# Power_CU_Schematic.net
KiCad netlist of a schematic drawn in Altium Designer
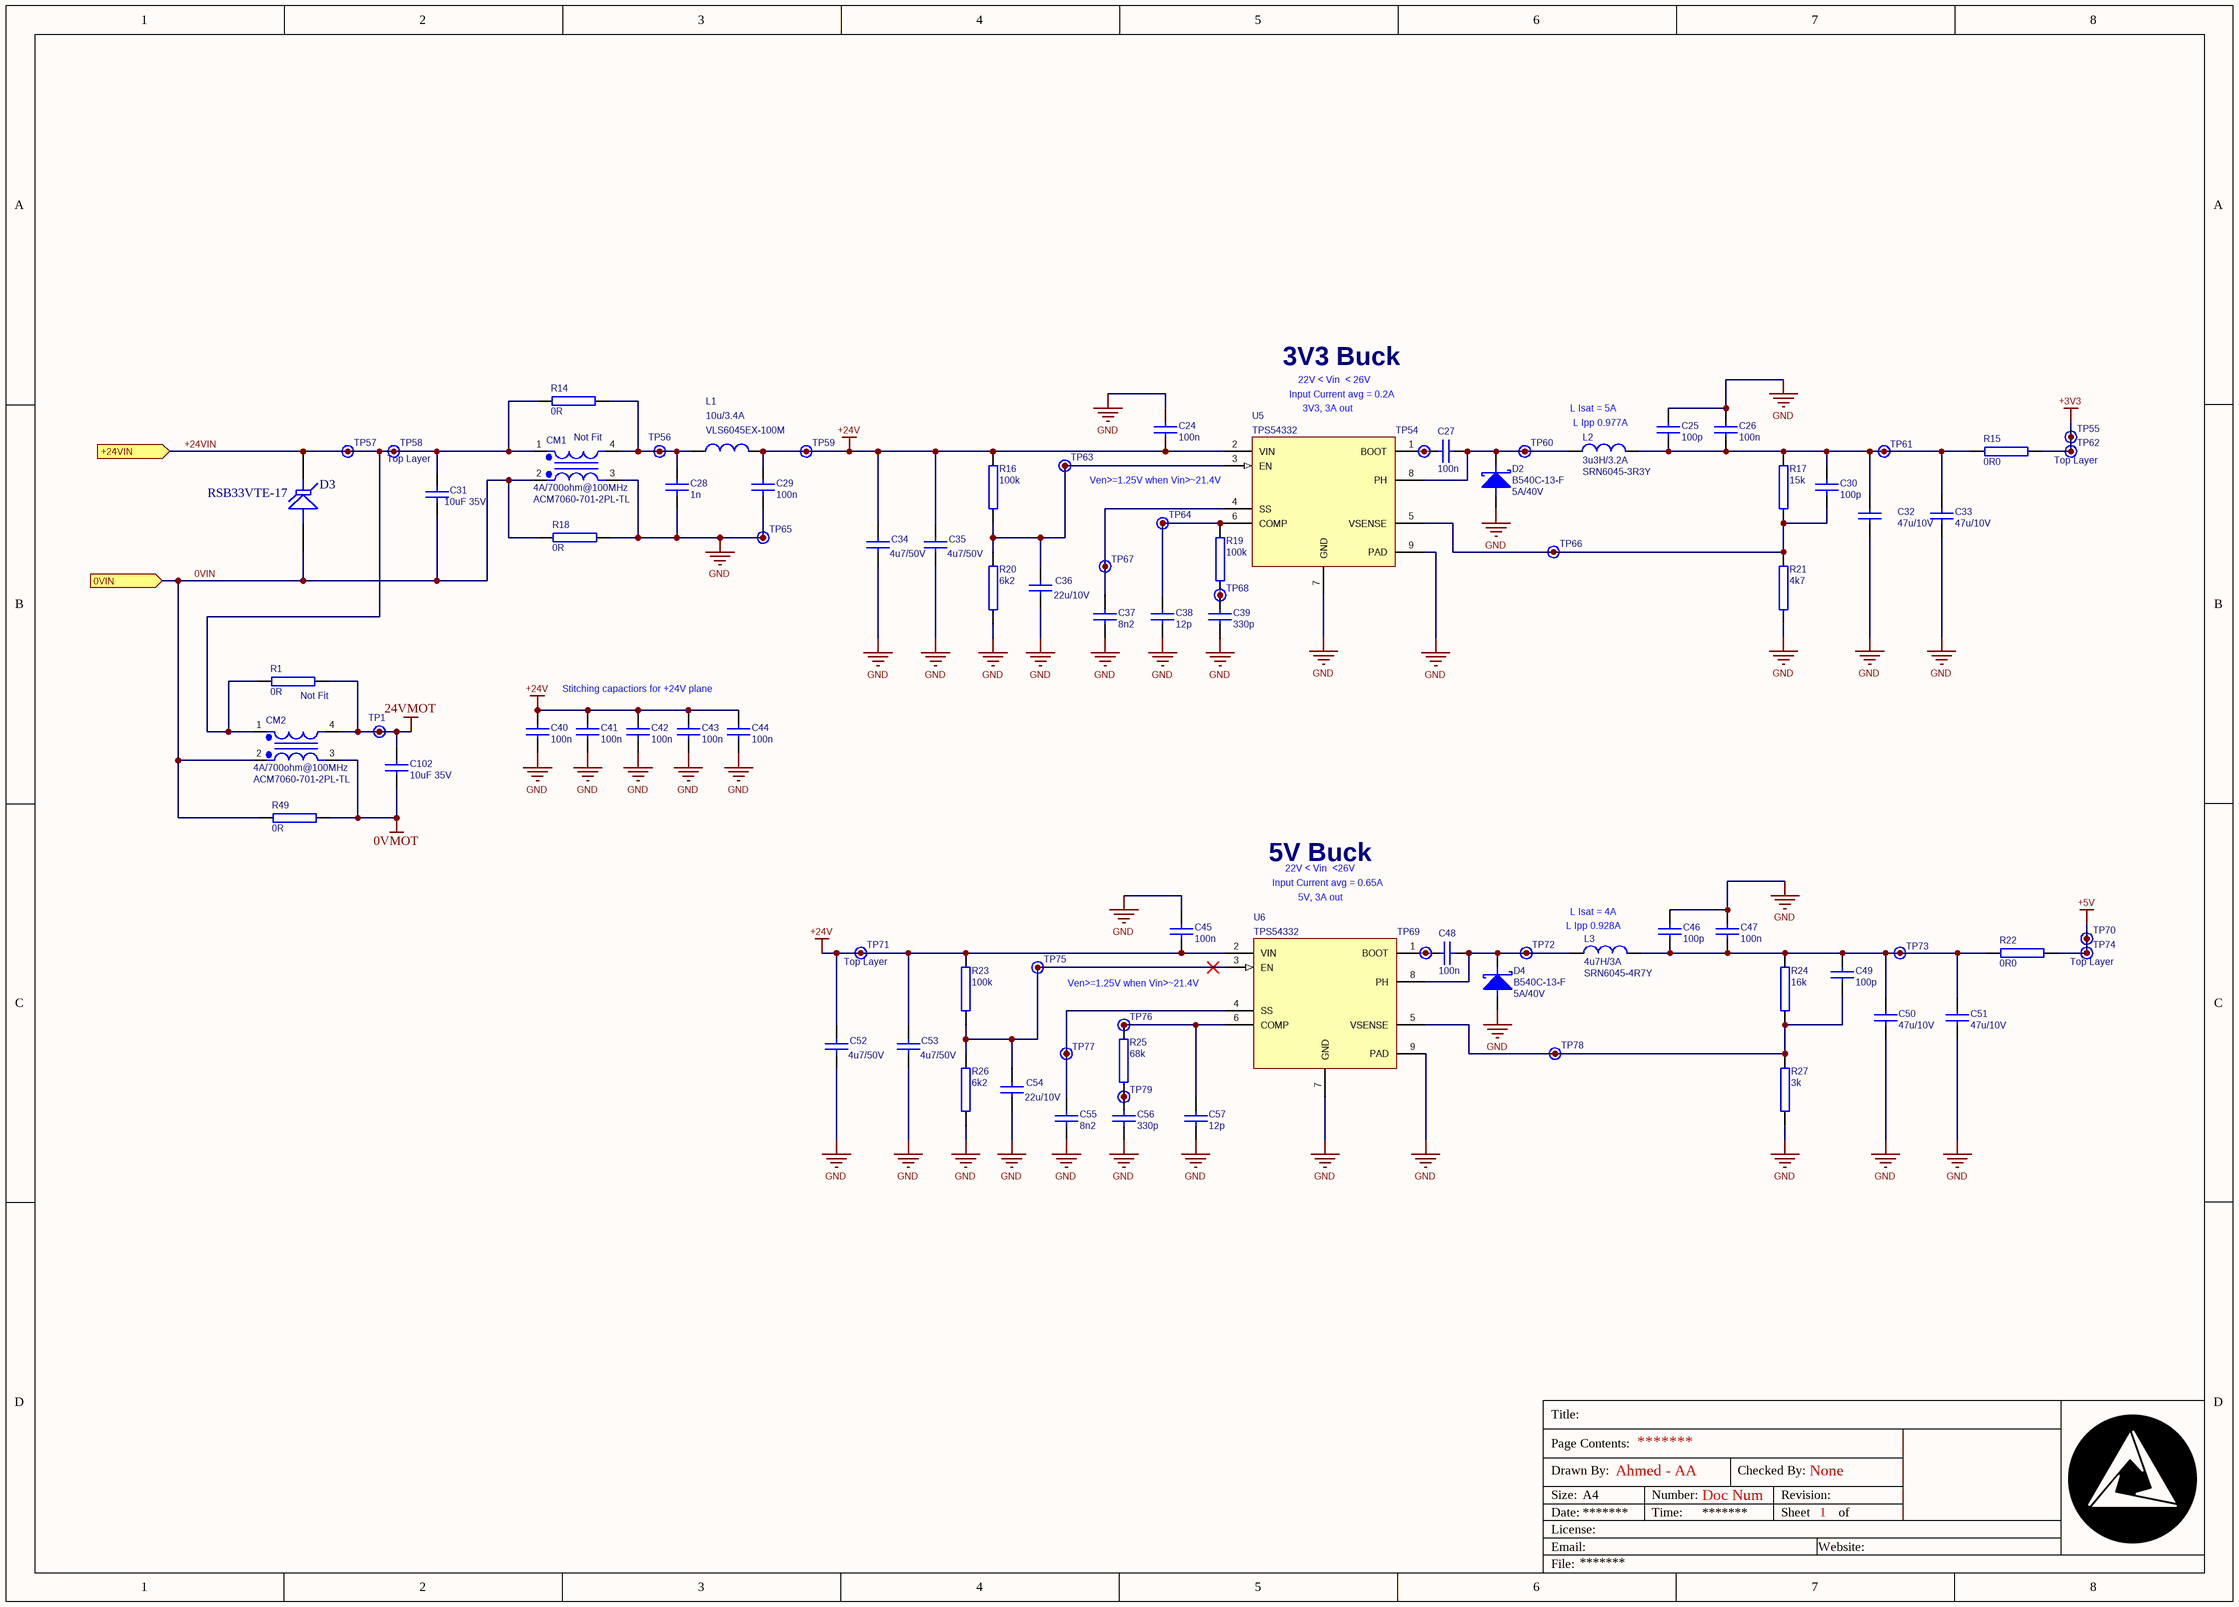
[diagram p0: Power_CU Schematic.SchDoc]

(export (version "E")
  (design (tool "Eeschema 10.0.6"))
  (components
    (comp (ref "C24")
      (value "100n")
      (footprint "CAPC1608X09N(0603)")
      (description "Capacitor, Ceramic, 50V, ±10%, X7R, -55°C to 125°C")
      (fields (field (name "02 PART NUMBER") "GRM188R71H104KA93D") (field (name "12 AUTHOR") "D.Grace"))
      (libsource (lib "Ingenuity Master Capacitor Schematic Library") (part "GRM188R71H104KA93D"))
    )
    (comp (ref "C25")
      (value "100p")
      (footprint "CAPC1608X09N(0603)")
      (description "Capacitor, Ceramic, 50V, ±5%, C0G NP0, -55°C to 125°C")
      (fields (field (name "02 PART NUMBER") "GRM1885C1H101JA01D") (field (name "12 AUTHOR") "D.Grace"))
      (libsource (lib "Ingenuity Master Capacitor Schematic Library") (part "GRM1885C1H101JA01D"))
    )
    (comp (ref "C26")
      (value "100n")
      (footprint "CAPC1608X09N(0603)")
      (description "Capacitor, Ceramic, 50V, ±10%, X7R, -55°C to 125°C")
      (fields (field (name "02 PART NUMBER") "GRM188R71H104KA93D") (field (name "12 AUTHOR") "D.Grace"))
      (libsource (lib "Ingenuity Master Capacitor Schematic Library") (part "GRM188R71H104KA93D"))
    )
    (comp (ref "C27")
      (value "100n")
      (footprint "CAPC1608X09N(0603)")
      (description "Capacitor, Ceramic, 50V, ±10%, X7R, -55°C to 125°C")
      (fields (field (name "02 PART NUMBER") "GRM188R71H104KA93D") (field (name "12 AUTHOR") "D.Grace"))
      (libsource (lib "Ingenuity Master Capacitor Schematic Library") (part "GRM188R71H104KA93D"))
    )
    (comp (ref "C28")
      (value "1n")
      (footprint "CAPC1608X09N(0603)")
      (description "Capacitor, Ceramic, 50V, ±5%, C0G NP0, -55°C to 125°C")
      (fields (field (name "02 PART NUMBER") "GRM1885C1H102JA01D") (field (name "12 AUTHOR") "D.Grace"))
      (libsource (lib "Ingenuity Master Capacitor Schematic Library") (part "GRM1885C1H102JA01D"))
    )
    (comp (ref "C29")
      (value "100n")
      (footprint "CAPC1608X09N(0603)")
      (description "Capacitor, Ceramic, 50V, ±10%, X7R, -55°C to 125°C")
      (fields (field (name "02 PART NUMBER") "GRM188R71H104KA93D") (field (name "12 AUTHOR") "D.Grace"))
      (libsource (lib "Ingenuity Master Capacitor Schematic Library") (part "GRM188R71H104KA93D"))
    )
    (comp (ref "C30")
      (value "100p")
      (footprint "CAPC1608X09N(0603)")
      (description "Capacitor, Ceramic, 50V, ±5%, C0G NP0, -55°C to 125°C")
      (fields (field (name "02 PART NUMBER") "GRM1885C1H101JA01D") (field (name "12 AUTHOR") "D.Grace"))
      (libsource (lib "Ingenuity Master Capacitor Schematic Library") (part "GRM1885C1H101JA01D"))
    )
    (comp (ref "C31")
      (value "10uF 35V")
      (footprint "CAPC1608X09N(0603)")
      (description "Capacitor, Ceramic, 50V, ±20%,")
      (fields (field (name "02 PART NUMBER") "GRM1885C1H102JA01D") (field (name "12 AUTHOR") "D.Grace"))
      (libsource (lib "Ingenuity Master Capacitor Schematic Library") (part "GRM1885C1H102JA01D"))
    )
    (comp (ref "C32")
      (value "47u/10V")
      (footprint "CAPC2012X13N(0805)")
      (description "Capacitor, Ceramic, 10V, ±20%, X5R, -55°C to 85°C")
      (fields (field (name "02 PART NUMBER") "C2012X5R1A476M125AC") (field (name "12 AUTHOR") "K.Sukumar"))
      (libsource (lib "Ingenuity Master Capacitor Schematic Library") (part "C2012X5R1A476M125AC"))
    )
    (comp (ref "C33")
      (value "47u/10V")
      (footprint "CAPC2012X13N(0805)")
      (description "Capacitor, Ceramic, 10V, ±20%, X5R, -55°C to 85°C")
      (fields (field (name "02 PART NUMBER") "C2012X5R1A476M125AC") (field (name "12 AUTHOR") "K.Sukumar"))
      (libsource (lib "Ingenuity Master Capacitor Schematic Library") (part "C2012X5R1A476M125AC"))
    )
    (comp (ref "C34")
      (value "Cin")
      (footprint "CAPC3216X16N(1206)")
      (description "Capacitor, Ceramic, 50V, ±10%, X7R, -55°C to 125°C")
      (fields
        (field (name "02 PART NUMBER") "GRM31CR71H475KA12L")
        (field (name "04 VALUE") "4u7/50V")
        (field (name "12 AUTHOR") "D.Grace")
      )
      (libsource (lib "Ingenuity Master Capacitor Schematic Library") (part "GRM31CR71H475KA12L"))
    )
    (comp (ref "C35")
      (value "Cin")
      (footprint "CAPC3216X16N(1206)")
      (description "Capacitor, Ceramic, 50V, ±10%, X7R, -55°C to 125°C")
      (fields
        (field (name "02 PART NUMBER") "GRM31CR71H475KA12L")
        (field (name "04 VALUE") "4u7/50V")
        (field (name "12 AUTHOR") "D.Grace")
      )
      (libsource (lib "Ingenuity Master Capacitor Schematic Library") (part "GRM31CR71H475KA12L"))
    )
    (comp (ref "C36")
      (value "22u/10V")
      (footprint "CAPC1608X09N(0603)")
      (description "Capacitor, Ceramic, 10V, ±20%, X5R, -55°C to 85°C")
      (fields (field (name "02 PART NUMBER") "C1608X5R1A226M080AC") (field (name "12 AUTHOR") "K.Sukumar"))
      (libsource (lib "Ingenuity Master Capacitor Schematic Library") (part "C1608X5R1A226M080AC"))
    )
    (comp (ref "C37")
      (value "8n2")
      (footprint "CAPC1608X09N(0603)")
      (description "Capacitor, Ceramic, 50V, ±10%, X7R, -55°C to 125°C")
      (fields (field (name "02 PART NUMBER") "GRM188R71H822KA01D") (field (name "12 AUTHOR") "D.Grace"))
      (libsource (lib "Ingenuity Master Capacitor Schematic Library") (part "GRM188R71H822KA01D"))
    )
    (comp (ref "C38")
      (value "12p")
      (footprint "CAPC1608X09N(0603)")
      (description "Capacitor, Ceramic, 50V, ±5%, C0G NP0, -55°C to 125°C")
      (fields (field (name "02 PART NUMBER") "GRM1885C1H120JA01D") (field (name "12 AUTHOR") "D.Grace"))
      (libsource (lib "Ingenuity Master Capacitor Schematic Library") (part "GRM1885C1H120JA01D"))
    )
    (comp (ref "C39")
      (value "330p")
      (footprint "CAPC1608X09N(0603)")
      (description "Capacitor, Ceramic, 50V, ±10%, X7R, -55°C to 125°C")
      (fields (field (name "02 PART NUMBER") "GRM188R71H331KA01D") (field (name "12 AUTHOR") "M.Fineschi"))
      (libsource (lib "D0001310 Trophon EPR GUI Carrier Board Schematic Library (1_0)") (part "GRM188R71H331KA01D"))
    )
    (comp (ref "C40")
      (value "100n")
      (footprint "CAPC1608X09N(0603)")
      (description "Capacitor, Ceramic, 50V, ±10%, X7R, -55°C to 125°C")
      (fields (field (name "02 PART NUMBER") "GRM188R71H104KA93D") (field (name "12 AUTHOR") "D.Grace"))
      (libsource (lib "Ingenuity Master Capacitor Schematic Library") (part "GRM188R71H104KA93D"))
    )
    (comp (ref "C41")
      (value "100n")
      (footprint "CAPC1608X09N(0603)")
      (description "Capacitor, Ceramic, 50V, ±10%, X7R, -55°C to 125°C")
      (fields (field (name "02 PART NUMBER") "GRM188R71H104KA93D") (field (name "12 AUTHOR") "D.Grace"))
      (libsource (lib "Ingenuity Master Capacitor Schematic Library") (part "GRM188R71H104KA93D"))
    )
    (comp (ref "C42")
      (value "100n")
      (footprint "CAPC1608X09N(0603)")
      (description "Capacitor, Ceramic, 50V, ±10%, X7R, -55°C to 125°C")
      (fields (field (name "02 PART NUMBER") "GRM188R71H104KA93D") (field (name "12 AUTHOR") "D.Grace"))
      (libsource (lib "Ingenuity Master Capacitor Schematic Library") (part "GRM188R71H104KA93D"))
    )
    (comp (ref "C43")
      (value "100n")
      (footprint "CAPC1608X09N(0603)")
      (description "Capacitor, Ceramic, 50V, ±10%, X7R, -55°C to 125°C")
      (fields (field (name "02 PART NUMBER") "GRM188R71H104KA93D") (field (name "12 AUTHOR") "D.Grace"))
      (libsource (lib "Ingenuity Master Capacitor Schematic Library") (part "GRM188R71H104KA93D"))
    )
    (comp (ref "C44")
      (value "100n")
      (footprint "CAPC1608X09N(0603)")
      (description "Capacitor, Ceramic, 50V, ±10%, X7R, -55°C to 125°C")
      (fields (field (name "02 PART NUMBER") "GRM188R71H104KA93D") (field (name "12 AUTHOR") "D.Grace"))
      (libsource (lib "Ingenuity Master Capacitor Schematic Library") (part "GRM188R71H104KA93D"))
    )
    (comp (ref "C45")
      (value "100n")
      (footprint "CAPC1608X09N(0603)")
      (description "Capacitor, Ceramic, 50V, ±10%, X7R, -55°C to 125°C")
      (fields (field (name "02 PART NUMBER") "GRM188R71H104KA93D") (field (name "12 AUTHOR") "D.Grace"))
      (libsource (lib "Ingenuity Master Capacitor Schematic Library") (part "GRM188R71H104KA93D"))
    )
    (comp (ref "C46")
      (value "100p")
      (footprint "CAPC1608X09N(0603)")
      (description "Capacitor, Ceramic, 50V, ±5%, C0G NP0, -55°C to 125°C")
      (fields (field (name "02 PART NUMBER") "GRM1885C1H101JA01D") (field (name "12 AUTHOR") "D.Grace"))
      (libsource (lib "Ingenuity Master Capacitor Schematic Library") (part "GRM1885C1H101JA01D"))
    )
    (comp (ref "C47")
      (value "100n")
      (footprint "CAPC1608X09N(0603)")
      (description "Capacitor, Ceramic, 50V, ±10%, X7R, -55°C to 125°C")
      (fields (field (name "02 PART NUMBER") "GRM188R71H104KA93D") (field (name "12 AUTHOR") "D.Grace"))
      (libsource (lib "Ingenuity Master Capacitor Schematic Library") (part "GRM188R71H104KA93D"))
    )
    (comp (ref "C48")
      (value "100n")
      (footprint "CAPC1608X09N(0603)")
      (description "Capacitor, Ceramic, 50V, ±10%, X7R, -55°C to 125°C")
      (fields (field (name "02 PART NUMBER") "GRM188R71H104KA93D") (field (name "12 AUTHOR") "D.Grace"))
      (libsource (lib "Ingenuity Master Capacitor Schematic Library") (part "GRM188R71H104KA93D"))
    )
    (comp (ref "C49")
      (value "100p")
      (footprint "CAPC1608X09N(0603)")
      (description "Capacitor, Ceramic, 50V, ±5%, C0G NP0, -55°C to 125°C")
      (fields (field (name "02 PART NUMBER") "GRM1885C1H101JA01D") (field (name "12 AUTHOR") "D.Grace"))
      (libsource (lib "Ingenuity Master Capacitor Schematic Library") (part "GRM1885C1H101JA01D"))
    )
    (comp (ref "C50")
      (value "47u/10V")
      (footprint "CAPC2012X13N(0805)")
      (description "Capacitor, Ceramic, 10V, ±20%, X5R, -55°C to 85°C")
      (fields (field (name "02 PART NUMBER") "C2012X5R1A476M125AC") (field (name "12 AUTHOR") "K.Sukumar"))
      (libsource (lib "Ingenuity Master Capacitor Schematic Library") (part "C2012X5R1A476M125AC"))
    )
    (comp (ref "C51")
      (value "47u/10V")
      (footprint "CAPC2012X13N(0805)")
      (description "Capacitor, Ceramic, 10V, ±20%, X5R, -55°C to 85°C")
      (fields (field (name "02 PART NUMBER") "C2012X5R1A476M125AC") (field (name "12 AUTHOR") "K.Sukumar"))
      (libsource (lib "Ingenuity Master Capacitor Schematic Library") (part "C2012X5R1A476M125AC"))
    )
    (comp (ref "C52")
      (value "Cin")
      (footprint "CAPC3216X16N(1206)")
      (description "Capacitor, Ceramic, 50V, ±10%, X7R, -55°C to 125°C")
      (fields
        (field (name "02 PART NUMBER") "GRM31CR71H475KA12L")
        (field (name "04 VALUE") "4u7/50V")
        (field (name "12 AUTHOR") "D.Grace")
      )
      (libsource (lib "Ingenuity Master Capacitor Schematic Library") (part "GRM31CR71H475KA12L"))
    )
    (comp (ref "C53")
      (value "Cin")
      (footprint "CAPC3216X16N(1206)")
      (description "Capacitor, Ceramic, 50V, ±10%, X7R, -55°C to 125°C")
      (fields
        (field (name "02 PART NUMBER") "GRM31CR71H475KA12L")
        (field (name "04 VALUE") "4u7/50V")
        (field (name "12 AUTHOR") "D.Grace")
      )
      (libsource (lib "Ingenuity Master Capacitor Schematic Library") (part "GRM31CR71H475KA12L"))
    )
    (comp (ref "C54")
      (value "22u/10V")
      (footprint "CAPC1608X09N(0603)")
      (description "Capacitor, Ceramic, 10V, ±20%, X5R, -55°C to 85°C")
      (fields (field (name "02 PART NUMBER") "C1608X5R1A226M080AC") (field (name "12 AUTHOR") "K.Sukumar"))
      (libsource (lib "Ingenuity Master Capacitor Schematic Library") (part "C1608X5R1A226M080AC"))
    )
    (comp (ref "C55")
      (value "8n2")
      (footprint "CAPC1608X09N(0603)")
      (description "Capacitor, Ceramic, 50V, ±10%, X7R, -55°C to 125°C")
      (fields (field (name "02 PART NUMBER") "GRM188R71H822KA01D") (field (name "12 AUTHOR") "D.Grace"))
      (libsource (lib "Ingenuity Master Capacitor Schematic Library") (part "GRM188R71H822KA01D"))
    )
    (comp (ref "C56")
      (value "330p")
      (footprint "CAPC1608X09N(0603)")
      (description "Capacitor, Ceramic, 50V, ±10%, X7R, -55°C to 125°C")
      (fields (field (name "02 PART NUMBER") "GRM188R71H331KA01D") (field (name "12 AUTHOR") "M.Fineschi"))
      (libsource (lib "D0001310 Trophon EPR GUI Carrier Board Schematic Library (1_0)") (part "GRM188R71H331KA01D"))
    )
    (comp (ref "C57")
      (value "12p")
      (footprint "CAPC1608X09N(0603)")
      (description "Capacitor, Ceramic, 50V, ±5%, C0G NP0, -55°C to 125°C")
      (fields (field (name "02 PART NUMBER") "GRM1885C1H120JA01D") (field (name "12 AUTHOR") "D.Grace"))
      (libsource (lib "Ingenuity Master Capacitor Schematic Library") (part "GRM1885C1H120JA01D"))
    )
    (comp (ref "C102")
      (value "10uF 35V")
      (footprint "CAPC1608X09N(0603)")
      (description "Capacitor, Ceramic, 50V, ±5%, C0G NP0, -55°C to 125°C")
      (libsource (lib "Ingenuity Master Capacitor Schematic Library") (part "GRM1885C1H102JA01D"))
    )
    (comp (ref "CM1")
      (value "4A/700ohm@100MHz")
      (footprint "ACM7060-701-2PL-TL")
      (description "Common Mode Choke, 4A, 500ohm min 700ohm typ @100MHz, 15mOhm Max,")
      (fields
        (field (name "07 ASSEMBLY OPTIONS") "Not Fit")
        (field (name "02 PART NUMBER") "ACM7060-701-2PL-TL")
        (field (name "12 AUTHOR") "D.Grace")
      )
      (libsource (lib "Mesh Nebuliser Schematic Library") (part "ACM7060-701-2PL-TL"))
    )
    (comp (ref "CM2")
      (value "4A/700ohm@100MHz")
      (footprint "ACM7060-701-2PL-TL")
      (description "Common Mode Choke, 4A, 500ohm min 700ohm typ @100MHz, 15mOhm Max,")
      (fields
        (field (name "07 ASSEMBLY OPTIONS") "Not Fit")
        (field (name "02 PART NUMBER") "ACM7060-701-2PL-TL")
        (field (name "12 AUTHOR") "D.Grace")
      )
      (libsource (lib "Mesh Nebuliser Schematic Library") (part "ACM7060-701-2PL-TL"))
    )
    (comp (ref "D2")
      (value "B540C-13-F")
      (footprint "B540C")
      (description "Diode, Schottky, Fast Recovery, 550mV @ 5A, 40V, 5A,  500ns, -55°C - +125°C")
      (fields (field (name "04 VALUE") "5A/40V") (field (name "12 AUTHOR") "J.McLachlan"))
      (libsource (lib "D0001310 Trophon EPR GUI Carrier Board Schematic Library (1_0)") (part "B540C-13-F"))
    )
    (comp (ref "D3")
      (value "RSB33VTE-17")
      (footprint "Miscellaneous Devices:425")
      (description "Transient Voltage Suppression (TVS) Diode")
      (fields (field (name "PUBLISHER") "Altium Limited"))
      (libsource (lib "Miscellaneous Devices") (part "Tranzorb"))
    )
    (comp (ref "D4")
      (value "B540C-13-F")
      (footprint "B540C")
      (description "Diode, Schottky, Fast Recovery, 550mV @ 5A, 40V, 5A,  500ns, -55°C - +125°C")
      (fields (field (name "04 VALUE") "5A/40V") (field (name "12 AUTHOR") "J.McLachlan"))
      (libsource (lib "D0001310 Trophon EPR GUI Carrier Board Schematic Library (1_0)") (part "B540C-13-F"))
    )
    (comp (ref "L1")
      (value "10u/3.4A")
      (footprint "VLP6045LT-100M")
      (description "Inductor, 10µH , 3.4A rated, 3.9A Saturation,61mOhm")
      (fields (field (name "02 PART NUMBER") "VLS6045EX-100M") (field (name "12 AUTHOR") "M.Fineschi"))
      (libsource (lib "D0001310 Trophon EPR GUI Carrier Board Schematic Library (1_0)") (part "VLP6045LT-100M"))
    )
    (comp (ref "L2")
      (value "3u3H/3.2A")
      (footprint "SRN6045-1R0Y")
      (description "Inductor, 3u3H , I = 3.2A, 30.2mOhm, SRF 27MHz, ±30%, 5A Saturation")
      (fields (field (name "02 PART NUMBER") "SRN6045-3R3Y") (field (name "12 AUTHOR") "J.McLachlan"))
      (libsource (lib "D0001310 Trophon EPR GUI Carrier Board Schematic Library (1_0)") (part "SRN6045-3R3Y"))
    )
    (comp (ref "L3")
      (value "4u7H/3A")
      (footprint "SRN6045-1R0Y")
      (description "Inductor, 4u7H , I = 3A, 37.6mOhm, SRF 22MHz, ±30%, 4A Saturation")
      (fields (field (name "02 PART NUMBER") "SRN6045-4R7Y") (field (name "12 AUTHOR") "J.McLachlan"))
      (libsource (lib "D0001310 Trophon EPR GUI Carrier Board Schematic Library (1_0)") (part "SRN6045-4R7Y"))
    )
    (comp (ref "R1")
      (value "0R")
      (footprint "RESC3116X07N(1206)")
      (description "Resistor, Thick Film, 0.25W, ±1%, ±100ppm/°C")
      (fields (field (name "02 PART NUMBER") "RC1206JR-070RL") (field (name "12 AUTHOR") "M.Fineschi"))
      (libsource (lib "D0001310 Trophon EPR GUI Carrier Board Schematic Library (1_0)") (part "RC1206JR-070RL"))
    )
    (comp (ref "R14")
      (value "0R")
      (footprint "RESC3116X07N(1206)")
      (description "Resistor, Thick Film, 0.25W, ±1%, ±100ppm/°C")
      (fields (field (name "02 PART NUMBER") "RC1206JR-070RL") (field (name "12 AUTHOR") "M.Fineschi"))
      (libsource (lib "D0001310 Trophon EPR GUI Carrier Board Schematic Library (1_0)") (part "RC1206JR-070RL"))
    )
    (comp (ref "R15")
      (value "0R0")
      (footprint "RESC1608X06N(0603)")
      (description "Resistor, Thick Film, 0.1W, ±1%, ±100ppm/°C")
      (fields
        (field (name "02 PART NUMBER") "RC1608J000CS")
        (field (name "13 REVIEWED BY") "P.Moutzouris")
        (field (name "12 AUTHOR") "K.Sukumar")
      )
      (libsource (lib "Ingenuity Master Resistor 0603 Schematic Library") (part "RC1608J000CS"))
    )
    (comp (ref "R16")
      (value "100k")
      (footprint "RESC1608X06N(0603)")
      (description "Resistor, Thick Film, 0.1W, ±1%, ±100ppm/°C")
      (fields
        (field (name "02 PART NUMBER") "RC0603FR-07100KL")
        (field (name "13 REVIEWED BY") "P.Moutzouris")
        (field (name "12 AUTHOR") "D.Grace")
      )
      (libsource (lib "Ingenuity Master Resistor 0603 Schematic Library") (part "RC0603FR-07100KL"))
    )
    (comp (ref "R17")
      (value "15k")
      (footprint "RESC1608X06N(0603)")
      (description "Resistor, Thick Film, 0.1W, ±1%, ±100ppm/°C")
      (fields
        (field (name "02 PART NUMBER") "RC0603FR-0715KL")
        (field (name "13 REVIEWED BY") "P.Moutzouris")
        (field (name "12 AUTHOR") "D.Grace")
      )
      (libsource (lib "Ingenuity Master Resistor 0603 Schematic Library") (part "RC0603FR-0715KL"))
    )
    (comp (ref "R18")
      (value "0R")
      (footprint "RESC3116X07N(1206)")
      (description "Resistor, Thick Film, 0.25W, ±1%, ±100ppm/°C")
      (fields (field (name "02 PART NUMBER") "RC1206JR-070RL") (field (name "12 AUTHOR") "M.Fineschi"))
      (libsource (lib "D0001310 Trophon EPR GUI Carrier Board Schematic Library (1_0)") (part "RC1206JR-070RL"))
    )
    (comp (ref "R19")
      (value "100k")
      (footprint "RESC1608X06N(0603)")
      (description "Resistor, Thick Film, 0.1W, ±1%, ±100ppm/°C")
      (fields
        (field (name "02 PART NUMBER") "RC0603FR-07100KL")
        (field (name "13 REVIEWED BY") "P.Moutzouris")
        (field (name "12 AUTHOR") "D.Grace")
      )
      (libsource (lib "Ingenuity Master Resistor 0603 Schematic Library") (part "RC0603FR-07100KL"))
    )
    (comp (ref "R20")
      (value "6k2")
      (footprint "RESC1608X06N(0603)")
      (description "Resistor, Thick Film, 0.1W, ±1%, ±100ppm/°C")
      (fields
        (field (name "02 PART NUMBER") "RC0603FR-076K2L")
        (field (name "13 REVIEWED BY") "P.Moutzouris")
        (field (name "12 AUTHOR") "D.Grace")
      )
      (libsource (lib "Ingenuity Master Resistor 0603 Schematic Library") (part "RC0603FR-076K2L"))
    )
    (comp (ref "R21")
      (value "4k7")
      (footprint "RESC1608X06N(0603)")
      (description "Resistor, Thick Film, 0.1W, ±1%, ±100ppm/°C")
      (fields
        (field (name "02 PART NUMBER") "RC0603FR-074K7L")
        (field (name "13 REVIEWED BY") "P.Moutzouris")
        (field (name "12 AUTHOR") "D.Grace")
      )
      (libsource (lib "Ingenuity Master Resistor 0603 Schematic Library") (part "RC0603FR-074K7L"))
    )
    (comp (ref "R22")
      (value "0R0")
      (footprint "RESC1608X06N(0603)")
      (description "Resistor, Thick Film, 0.1W, ±1%, ±100ppm/°C")
      (fields
        (field (name "02 PART NUMBER") "RC1608J000CS")
        (field (name "13 REVIEWED BY") "P.Moutzouris")
        (field (name "12 AUTHOR") "K.Sukumar")
      )
      (libsource (lib "Ingenuity Master Resistor 0603 Schematic Library") (part "RC1608J000CS"))
    )
    (comp (ref "R23")
      (value "100k")
      (footprint "RESC1608X06N(0603)")
      (description "Resistor, Thick Film, 0.1W, ±1%, ±100ppm/°C")
      (fields
        (field (name "02 PART NUMBER") "RC0603FR-07100KL")
        (field (name "13 REVIEWED BY") "P.Moutzouris")
        (field (name "12 AUTHOR") "D.Grace")
      )
      (libsource (lib "Ingenuity Master Resistor 0603 Schematic Library") (part "RC0603FR-07100KL"))
    )
    (comp (ref "R24")
      (value "16k")
      (footprint "RESC1608X06N(0603)")
      (description "Resistor, Thick Film, 0.1W, ±1%, ±100ppm/°C")
      (fields
        (field (name "02 PART NUMBER") "RC0603FR-0716KL")
        (field (name "13 REVIEWED BY") "P.Moutzouris")
        (field (name "12 AUTHOR") "D.Grace")
      )
      (libsource (lib "Ingenuity Master Resistor 0603 Schematic Library") (part "RC0603FR-0716KL"))
    )
    (comp (ref "R25")
      (value "68k")
      (footprint "RESC1608X06N(0603)")
      (description "Resistor, Thick Film, 0.1W, ±1%, ±100ppm/°C")
      (fields
        (field (name "02 PART NUMBER") "RC0603FR-0768KL")
        (field (name "13 REVIEWED BY") "P.Moutzouris")
        (field (name "12 AUTHOR") "D.Grace")
      )
      (libsource (lib "Ingenuity Master Resistor 0603 Schematic Library") (part "RC0603FR-0768KL"))
    )
    (comp (ref "R26")
      (value "6k2")
      (footprint "RESC1608X06N(0603)")
      (description "Resistor, Thick Film, 0.1W, ±1%, ±100ppm/°C")
      (fields
        (field (name "02 PART NUMBER") "RC0603FR-076K2L")
        (field (name "13 REVIEWED BY") "P.Moutzouris")
        (field (name "12 AUTHOR") "D.Grace")
      )
      (libsource (lib "Ingenuity Master Resistor 0603 Schematic Library") (part "RC0603FR-076K2L"))
    )
    (comp (ref "R27")
      (value "3k")
      (footprint "RESC1608X06N(0603)")
      (description "Resistor, Thick Film, 0.1W, ±1%, ±100ppm/°C")
      (fields
        (field (name "02 PART NUMBER") "RC0603FR-073KL")
        (field (name "13 REVIEWED BY") "P.Moutzouris")
        (field (name "12 AUTHOR") "D.Grace")
      )
      (libsource (lib "Ingenuity Master Resistor 0603 Schematic Library") (part "RC0603FR-073KL"))
    )
    (comp (ref "R49")
      (value "0R")
      (footprint "RESC3116X07N(1206)")
      (description "Resistor, Thick Film, 0.25W, ±1%, ±100ppm/°C")
      (fields (field (name "02 PART NUMBER") "RC1206JR-070RL") (field (name "12 AUTHOR") "M.Fineschi"))
      (libsource (lib "D0001310 Trophon EPR GUI Carrier Board Schematic Library (1_0)") (part "RC1206JR-070RL"))
    )
    (comp (ref "TP1")
      (value "LFX_P")
      (footprint "Test Point 1mm")
      (description "Test Point")
      (fields (field (name "12 AUTHOR") "D.Grace"))
      (libsource (lib "Mesh Nebuliser Schematic Library") (part "Test Point"))
    )
    (comp (ref "TP54")
      (value "LFX_P")
      (footprint "Test Point 1mm")
      (description "Test Point")
      (fields (field (name "12 AUTHOR") "D.Grace"))
      (libsource (lib "Mesh Nebuliser Schematic Library") (part "Test Point"))
    )
    (comp (ref "TP55")
      (value "LFX_P")
      (footprint "Test Point 1mm")
      (description "Test Point")
      (fields (field (name "12 AUTHOR") "D.Grace"))
      (libsource (lib "Mesh Nebuliser Schematic Library") (part "Test Point"))
    )
    (comp (ref "TP56")
      (value "LFX_P")
      (footprint "Test Point 1mm")
      (description "Test Point")
      (fields (field (name "12 AUTHOR") "D.Grace"))
      (libsource (lib "Mesh Nebuliser Schematic Library") (part "Test Point"))
    )
    (comp (ref "TP57")
      (value "LFX_P")
      (footprint "Test Point 1mm")
      (description "Test Point")
      (fields (field (name "12 AUTHOR") "D.Grace"))
      (libsource (lib "Mesh Nebuliser Schematic Library") (part "Test Point"))
    )
    (comp (ref "TP58")
      (value "LFX_P")
      (footprint "Test Point 1mm")
      (description "Test Point")
      (fields (field (name "NOTES") "Top Layer") (field (name "12 AUTHOR") "D.Grace"))
      (libsource (lib "Mesh Nebuliser Schematic Library") (part "Test Point"))
    )
    (comp (ref "TP59")
      (value "LFX_P")
      (footprint "Test Point 1mm")
      (description "Test Point")
      (fields (field (name "12 AUTHOR") "D.Grace"))
      (libsource (lib "Mesh Nebuliser Schematic Library") (part "Test Point"))
    )
    (comp (ref "TP60")
      (value "LFX_P")
      (footprint "Test Point 1mm")
      (description "Test Point")
      (fields (field (name "12 AUTHOR") "D.Grace"))
      (libsource (lib "Mesh Nebuliser Schematic Library") (part "Test Point"))
    )
    (comp (ref "TP61")
      (value "LFX_P")
      (footprint "Test Point 1mm")
      (description "Test Point")
      (fields (field (name "12 AUTHOR") "D.Grace"))
      (libsource (lib "Mesh Nebuliser Schematic Library") (part "Test Point"))
    )
    (comp (ref "TP62")
      (value "LFX_P")
      (footprint "Test Point 1mm")
      (description "Test Point")
      (fields (field (name "NOTES") "Top Layer") (field (name "12 AUTHOR") "D.Grace"))
      (libsource (lib "Mesh Nebuliser Schematic Library") (part "Test Point"))
    )
    (comp (ref "TP63")
      (value "LFX_P")
      (footprint "Test Point 1mm")
      (description "Test Point")
      (fields (field (name "12 AUTHOR") "D.Grace"))
      (libsource (lib "Mesh Nebuliser Schematic Library") (part "Test Point"))
    )
    (comp (ref "TP64")
      (value "LFX_P")
      (footprint "Test Point 1mm")
      (description "Test Point")
      (fields (field (name "12 AUTHOR") "D.Grace"))
      (libsource (lib "Mesh Nebuliser Schematic Library") (part "Test Point"))
    )
    (comp (ref "TP65")
      (value "LFX_P")
      (footprint "Test Point 1mm")
      (description "Test Point")
      (fields (field (name "12 AUTHOR") "D.Grace"))
      (libsource (lib "Mesh Nebuliser Schematic Library") (part "Test Point"))
    )
    (comp (ref "TP66")
      (value "LFX_P")
      (footprint "Test Point 1mm")
      (description "Test Point")
      (fields (field (name "12 AUTHOR") "D.Grace"))
      (libsource (lib "Mesh Nebuliser Schematic Library") (part "Test Point"))
    )
    (comp (ref "TP67")
      (value "LFX_P")
      (footprint "Test Point 1mm")
      (description "Test Point")
      (fields (field (name "12 AUTHOR") "D.Grace"))
      (libsource (lib "Mesh Nebuliser Schematic Library") (part "Test Point"))
    )
    (comp (ref "TP68")
      (value "LFX_P")
      (footprint "Test Point 1mm")
      (description "Test Point")
      (fields (field (name "12 AUTHOR") "D.Grace"))
      (libsource (lib "Mesh Nebuliser Schematic Library") (part "Test Point"))
    )
    (comp (ref "TP69")
      (value "LFX_P")
      (footprint "Test Point 1mm")
      (description "Test Point")
      (fields (field (name "12 AUTHOR") "D.Grace"))
      (libsource (lib "Mesh Nebuliser Schematic Library") (part "Test Point"))
    )
    (comp (ref "TP70")
      (value "LFX_P")
      (footprint "Test Point 1mm")
      (description "Test Point")
      (fields (field (name "12 AUTHOR") "D.Grace"))
      (libsource (lib "Mesh Nebuliser Schematic Library") (part "Test Point"))
    )
    (comp (ref "TP71")
      (value "LFX_P")
      (footprint "Test Point 1mm")
      (description "Test Point")
      (fields (field (name "NOTES") "Top Layer") (field (name "12 AUTHOR") "D.Grace"))
      (libsource (lib "Mesh Nebuliser Schematic Library") (part "Test Point"))
    )
    (comp (ref "TP72")
      (value "LFX_P")
      (footprint "Test Point 1mm")
      (description "Test Point")
      (fields (field (name "12 AUTHOR") "D.Grace"))
      (libsource (lib "Mesh Nebuliser Schematic Library") (part "Test Point"))
    )
    (comp (ref "TP73")
      (value "LFX_P")
      (footprint "Test Point 1mm")
      (description "Test Point")
      (fields (field (name "12 AUTHOR") "D.Grace"))
      (libsource (lib "Mesh Nebuliser Schematic Library") (part "Test Point"))
    )
    (comp (ref "TP74")
      (value "LFX_P")
      (footprint "Test Point 1mm")
      (description "Test Point")
      (fields (field (name "NOTES") "Top Layer") (field (name "12 AUTHOR") "D.Grace"))
      (libsource (lib "Mesh Nebuliser Schematic Library") (part "Test Point"))
    )
    (comp (ref "TP75")
      (value "LFX_P")
      (footprint "Test Point 1mm")
      (description "Test Point")
      (fields (field (name "12 AUTHOR") "D.Grace"))
      (libsource (lib "Mesh Nebuliser Schematic Library") (part "Test Point"))
    )
    (comp (ref "TP76")
      (value "LFX_P")
      (footprint "Test Point 1mm")
      (description "Test Point")
      (fields (field (name "12 AUTHOR") "D.Grace"))
      (libsource (lib "Mesh Nebuliser Schematic Library") (part "Test Point"))
    )
    (comp (ref "TP77")
      (value "LFX_P")
      (footprint "Test Point 1mm")
      (description "Test Point")
      (fields (field (name "12 AUTHOR") "D.Grace"))
      (libsource (lib "Mesh Nebuliser Schematic Library") (part "Test Point"))
    )
    (comp (ref "TP78")
      (value "LFX_P")
      (footprint "Test Point 1mm")
      (description "Test Point")
      (fields (field (name "12 AUTHOR") "D.Grace"))
      (libsource (lib "Mesh Nebuliser Schematic Library") (part "Test Point"))
    )
    (comp (ref "TP79")
      (value "LFX_P")
      (footprint "Test Point 1mm")
      (description "Test Point")
      (fields (field (name "12 AUTHOR") "D.Grace"))
      (libsource (lib "Mesh Nebuliser Schematic Library") (part "Test Point"))
    )
    (comp (ref "U5")
      (value "TPS54332")
      (footprint "SOIC127P600X170_HS-9N_b")
      (description "Step Down, Adjustable, Vomin = 0.8V, Vin = 3.5 - 28V, Fs = 1MHz, Io = 3.5A, -40  ~ 125C")
      (fields (field (name "12 AUTHOR") "M.Fineschi"))
      (libsource (lib "D0001310 Trophon EPR GUI Carrier Board Schematic Library (1_0)") (part "TPS54332"))
    )
    (comp (ref "U6")
      (value "TPS54332")
      (footprint "SOIC127P600X170_HS-9N_b")
      (description "Step Down, Adjustable, Vomin = 0.8V, Vin = 3.5 - 28V, Fs = 1MHz, Io = 3.5A, -40  ~ 125C")
      (fields (field (name "12 AUTHOR") "M.Fineschi"))
      (libsource (lib "D0001310 Trophon EPR GUI Carrier Board Schematic Library (1_0)") (part "TPS54332"))
    )
  )
  (nets
    (net (code "1") (name "+3V3") (class "Default")
      (node (ref "R15") (pin "2") (pintype "passive"))
      (node (ref "TP55") (pin "TP") (pinfunction "TP_TP") (pintype "passive"))
      (node (ref "TP62") (pin "TP") (pinfunction "TP_TP") (pintype "passive"))
    )
    (net (code "2") (name "+5V") (class "Default")
      (node (ref "R22") (pin "2") (pintype "passive"))
      (node (ref "TP70") (pin "TP") (pinfunction "TP_TP") (pintype "passive"))
      (node (ref "TP74") (pin "TP") (pinfunction "TP_TP") (pintype "passive"))
    )
    (net (code "3") (name "+24V") (class "Default")
      (node (ref "C24") (pin "2") (pinfunction "2_2") (pintype "passive"))
      (node (ref "C29") (pin "1") (pinfunction "1_1") (pintype "passive"))
      (node (ref "C34") (pin "2") (pinfunction "2_2") (pintype "passive"))
      (node (ref "C35") (pin "2") (pinfunction "2_2") (pintype "passive"))
      (node (ref "C40") (pin "1") (pinfunction "1_1") (pintype "passive"))
      (node (ref "C41") (pin "1") (pinfunction "1_1") (pintype "passive"))
      (node (ref "C42") (pin "1") (pinfunction "1_1") (pintype "passive"))
      (node (ref "C43") (pin "1") (pinfunction "1_1") (pintype "passive"))
      (node (ref "C44") (pin "1") (pinfunction "1_1") (pintype "passive"))
      (node (ref "C45") (pin "2") (pinfunction "2_2") (pintype "passive"))
      (node (ref "C52") (pin "2") (pinfunction "2_2") (pintype "passive"))
      (node (ref "C53") (pin "2") (pinfunction "2_2") (pintype "passive"))
      (node (ref "L1") (pin "2") (pinfunction "2_2") (pintype "passive"))
      (node (ref "R16") (pin "2") (pintype "passive"))
      (node (ref "R23") (pin "2") (pintype "passive"))
      (node (ref "TP59") (pin "TP") (pinfunction "TP_TP") (pintype "passive"))
      (node (ref "TP71") (pin "TP") (pinfunction "TP_TP") (pintype "passive"))
      (node (ref "U5") (pin "2") (pinfunction "VIN_2") (pintype "power_in"))
      (node (ref "U6") (pin "2") (pinfunction "VIN_2") (pintype "power_in"))
    )
    (net (code "4") (name "/+24VIN") (class "Default")
      (node (ref "C31") (pin "2") (pinfunction "2_2") (pintype "passive"))
      (node (ref "CM1") (pin "1") (pinfunction "1_1") (pintype "passive"))
      (node (ref "CM2") (pin "1") (pinfunction "1_1") (pintype "passive"))
      (node (ref "D3") (pin "2") (pinfunction "K_2") (pintype "passive"))
      (node (ref "R1") (pin "1") (pintype "passive"))
      (node (ref "R14") (pin "1") (pintype "passive"))
      (node (ref "TP57") (pin "TP") (pinfunction "TP_TP") (pintype "passive"))
      (node (ref "TP58") (pin "TP") (pinfunction "TP_TP") (pintype "passive"))
    )
    (net (code "5") (name "/0VIN") (class "Default")
      (node (ref "C31") (pin "1") (pinfunction "1_1") (pintype "passive"))
      (node (ref "CM1") (pin "2") (pinfunction "2_2") (pintype "passive"))
      (node (ref "CM2") (pin "2") (pinfunction "2_2") (pintype "passive"))
      (node (ref "D3") (pin "1") (pinfunction "A_1") (pintype "passive"))
      (node (ref "R18") (pin "1") (pintype "passive"))
      (node (ref "R49") (pin "1") (pintype "passive"))
    )
    (net (code "6") (name "0VMOT") (class "Default")
      (node (ref "C102") (pin "1") (pinfunction "1_1") (pintype "passive"))
      (node (ref "CM2") (pin "3") (pinfunction "3_3") (pintype "passive"))
      (node (ref "R49") (pin "2") (pintype "passive"))
    )
    (net (code "7") (name "24VMOT") (class "Default")
      (node (ref "C102") (pin "2") (pinfunction "2_2") (pintype "passive"))
      (node (ref "CM2") (pin "4") (pinfunction "4_4") (pintype "passive"))
      (node (ref "R1") (pin "2") (pintype "passive"))
      (node (ref "TP1") (pin "TP") (pinfunction "TP_TP") (pintype "passive"))
    )
    (net (code "8") (name "GND") (class "Default")
      (node (ref "C24") (pin "1") (pinfunction "1_1") (pintype "passive"))
      (node (ref "C25") (pin "1") (pinfunction "1_1") (pintype "passive"))
      (node (ref "C26") (pin "1") (pinfunction "1_1") (pintype "passive"))
      (node (ref "C28") (pin "1") (pinfunction "1_1") (pintype "passive"))
      (node (ref "C29") (pin "2") (pinfunction "2_2") (pintype "passive"))
      (node (ref "C32") (pin "1") (pinfunction "1_1") (pintype "passive"))
      (node (ref "C33") (pin "1") (pinfunction "1_1") (pintype "passive"))
      (node (ref "C34") (pin "1") (pinfunction "1_1") (pintype "passive"))
      (node (ref "C35") (pin "1") (pinfunction "1_1") (pintype "passive"))
      (node (ref "C36") (pin "1") (pinfunction "1_1") (pintype "passive"))
      (node (ref "C37") (pin "1") (pinfunction "1_1") (pintype "passive"))
      (node (ref "C38") (pin "1") (pinfunction "1_1") (pintype "passive"))
      (node (ref "C39") (pin "1") (pinfunction "1_1") (pintype "passive"))
      (node (ref "C40") (pin "2") (pinfunction "2_2") (pintype "passive"))
      (node (ref "C41") (pin "2") (pinfunction "2_2") (pintype "passive"))
      (node (ref "C42") (pin "2") (pinfunction "2_2") (pintype "passive"))
      (node (ref "C43") (pin "2") (pinfunction "2_2") (pintype "passive"))
      (node (ref "C44") (pin "2") (pinfunction "2_2") (pintype "passive"))
      (node (ref "C45") (pin "1") (pinfunction "1_1") (pintype "passive"))
      (node (ref "C46") (pin "1") (pinfunction "1_1") (pintype "passive"))
      (node (ref "C47") (pin "1") (pinfunction "1_1") (pintype "passive"))
      (node (ref "C50") (pin "1") (pinfunction "1_1") (pintype "passive"))
      (node (ref "C51") (pin "1") (pinfunction "1_1") (pintype "passive"))
      (node (ref "C52") (pin "1") (pinfunction "1_1") (pintype "passive"))
      (node (ref "C53") (pin "1") (pinfunction "1_1") (pintype "passive"))
      (node (ref "C54") (pin "1") (pinfunction "1_1") (pintype "passive"))
      (node (ref "C55") (pin "1") (pinfunction "1_1") (pintype "passive"))
      (node (ref "C56") (pin "1") (pinfunction "1_1") (pintype "passive"))
      (node (ref "C57") (pin "1") (pinfunction "1_1") (pintype "passive"))
      (node (ref "CM1") (pin "3") (pinfunction "3_3") (pintype "passive"))
      (node (ref "D2") (pin "A") (pinfunction "A_A") (pintype "passive"))
      (node (ref "D4") (pin "A") (pinfunction "A_A") (pintype "passive"))
      (node (ref "R18") (pin "2") (pintype "passive"))
      (node (ref "R20") (pin "1") (pintype "passive"))
      (node (ref "R21") (pin "1") (pintype "passive"))
      (node (ref "R26") (pin "1") (pintype "passive"))
      (node (ref "R27") (pin "1") (pintype "passive"))
      (node (ref "TP65") (pin "TP") (pinfunction "TP_TP") (pintype "passive"))
      (node (ref "U5") (pin "7") (pinfunction "GND_7") (pintype "power_in"))
      (node (ref "U5") (pin "9") (pinfunction "PAD_9") (pintype "power_in"))
      (node (ref "U6") (pin "7") (pinfunction "GND_7") (pintype "power_in"))
      (node (ref "U6") (pin "9") (pinfunction "PAD_9") (pintype "power_in"))
    )
    (net (code "9") (name "Net-(C25-Pad2)") (class "Default")
      (node (ref "C25") (pin "2") (pinfunction "2_2") (pintype "passive"))
      (node (ref "C26") (pin "2") (pinfunction "2_2") (pintype "passive"))
      (node (ref "C30") (pin "1") (pinfunction "1_1") (pintype "passive"))
      (node (ref "C32") (pin "2") (pinfunction "2_2") (pintype "passive"))
      (node (ref "C33") (pin "2") (pinfunction "2_2") (pintype "passive"))
      (node (ref "L2") (pin "2") (pinfunction "2_2") (pintype "passive"))
      (node (ref "R15") (pin "1") (pintype "passive"))
      (node (ref "R17") (pin "2") (pintype "passive"))
      (node (ref "TP61") (pin "TP") (pinfunction "TP_TP") (pintype "passive"))
    )
    (net (code "10") (name "Net-(C28-Pad2)") (class "Default")
      (node (ref "C28") (pin "2") (pinfunction "2_2") (pintype "passive"))
      (node (ref "CM1") (pin "4") (pinfunction "4_4") (pintype "passive"))
      (node (ref "L1") (pin "1") (pinfunction "1_1") (pintype "passive"))
      (node (ref "R14") (pin "2") (pintype "passive"))
      (node (ref "TP56") (pin "TP") (pinfunction "TP_TP") (pintype "passive"))
    )
    (net (code "11") (name "Net-(C39-Pad2)") (class "Default")
      (node (ref "C39") (pin "2") (pinfunction "2_2") (pintype "passive"))
      (node (ref "R19") (pin "1") (pintype "passive"))
      (node (ref "TP68") (pin "TP") (pinfunction "TP_TP") (pintype "passive"))
    )
    (net (code "12") (name "Net-(C46-Pad2)") (class "Default")
      (node (ref "C46") (pin "2") (pinfunction "2_2") (pintype "passive"))
      (node (ref "C47") (pin "2") (pinfunction "2_2") (pintype "passive"))
      (node (ref "C49") (pin "1") (pinfunction "1_1") (pintype "passive"))
      (node (ref "C50") (pin "2") (pinfunction "2_2") (pintype "passive"))
      (node (ref "C51") (pin "2") (pinfunction "2_2") (pintype "passive"))
      (node (ref "L3") (pin "2") (pinfunction "2_2") (pintype "passive"))
      (node (ref "R22") (pin "1") (pintype "passive"))
      (node (ref "R24") (pin "2") (pintype "passive"))
      (node (ref "TP73") (pin "TP") (pinfunction "TP_TP") (pintype "passive"))
    )
    (net (code "13") (name "Net-(C56-Pad2)") (class "Default")
      (node (ref "C56") (pin "2") (pinfunction "2_2") (pintype "passive"))
      (node (ref "R25") (pin "1") (pintype "passive"))
      (node (ref "TP79") (pin "TP") (pinfunction "TP_TP") (pintype "passive"))
    )
    (net (code "14") (name "Net-(U5-BOOT)") (class "Default")
      (node (ref "C27") (pin "2") (pinfunction "2_2") (pintype "passive"))
      (node (ref "TP54") (pin "TP") (pinfunction "TP_TP") (pintype "passive"))
      (node (ref "U5") (pin "1") (pinfunction "BOOT_1") (pintype "power_in"))
    )
    (net (code "15") (name "Net-(U5-COMP)") (class "Default")
      (node (ref "C38") (pin "2") (pinfunction "2_2") (pintype "passive"))
      (node (ref "R19") (pin "2") (pintype "passive"))
      (node (ref "TP64") (pin "TP") (pinfunction "TP_TP") (pintype "passive"))
      (node (ref "U5") (pin "6") (pinfunction "COMP_6") (pintype "passive"))
    )
    (net (code "16") (name "Net-(U5-EN)") (class "Default")
      (node (ref "C36") (pin "2") (pinfunction "2_2") (pintype "passive"))
      (node (ref "R16") (pin "1") (pintype "passive"))
      (node (ref "R20") (pin "2") (pintype "passive"))
      (node (ref "TP63") (pin "TP") (pinfunction "TP_TP") (pintype "passive"))
      (node (ref "U5") (pin "3") (pinfunction "EN_3") (pintype "input"))
    )
    (net (code "17") (name "Net-(U5-PH)") (class "Default")
      (node (ref "C27") (pin "1") (pinfunction "1_1") (pintype "passive"))
      (node (ref "D2") (pin "K") (pinfunction "K_K") (pintype "passive"))
      (node (ref "L2") (pin "1") (pinfunction "1_1") (pintype "passive"))
      (node (ref "TP60") (pin "TP") (pinfunction "TP_TP") (pintype "passive"))
      (node (ref "U5") (pin "8") (pinfunction "PH_8") (pintype "power_in"))
    )
    (net (code "18") (name "Net-(U5-SS)") (class "Default")
      (node (ref "C37") (pin "2") (pinfunction "2_2") (pintype "passive"))
      (node (ref "TP67") (pin "TP") (pinfunction "TP_TP") (pintype "passive"))
      (node (ref "U5") (pin "4") (pinfunction "SS_4") (pintype "passive"))
    )
    (net (code "19") (name "Net-(U5-VSENSE)") (class "Default")
      (node (ref "C30") (pin "2") (pinfunction "2_2") (pintype "passive"))
      (node (ref "R17") (pin "1") (pintype "passive"))
      (node (ref "R21") (pin "2") (pintype "passive"))
      (node (ref "TP66") (pin "TP") (pinfunction "TP_TP") (pintype "passive"))
      (node (ref "U5") (pin "5") (pinfunction "VSENSE_5") (pintype "power_in"))
    )
    (net (code "20") (name "Net-(U6-BOOT)") (class "Default")
      (node (ref "C48") (pin "2") (pinfunction "2_2") (pintype "passive"))
      (node (ref "TP69") (pin "TP") (pinfunction "TP_TP") (pintype "passive"))
      (node (ref "U6") (pin "1") (pinfunction "BOOT_1") (pintype "power_in"))
    )
    (net (code "21") (name "Net-(U6-COMP)") (class "Default")
      (node (ref "C57") (pin "2") (pinfunction "2_2") (pintype "passive"))
      (node (ref "R25") (pin "2") (pintype "passive"))
      (node (ref "TP76") (pin "TP") (pinfunction "TP_TP") (pintype "passive"))
      (node (ref "U6") (pin "6") (pinfunction "COMP_6") (pintype "passive"))
    )
    (net (code "22") (name "Net-(U6-EN)") (class "Default")
      (node (ref "C54") (pin "2") (pinfunction "2_2") (pintype "passive"))
      (node (ref "R23") (pin "1") (pintype "passive"))
      (node (ref "R26") (pin "2") (pintype "passive"))
      (node (ref "TP75") (pin "TP") (pinfunction "TP_TP") (pintype "passive"))
      (node (ref "U6") (pin "3") (pinfunction "EN_3") (pintype "input"))
    )
    (net (code "23") (name "Net-(U6-PH)") (class "Default")
      (node (ref "C48") (pin "1") (pinfunction "1_1") (pintype "passive"))
      (node (ref "D4") (pin "K") (pinfunction "K_K") (pintype "passive"))
      (node (ref "L3") (pin "1") (pinfunction "1_1") (pintype "passive"))
      (node (ref "TP72") (pin "TP") (pinfunction "TP_TP") (pintype "passive"))
      (node (ref "U6") (pin "8") (pinfunction "PH_8") (pintype "power_in"))
    )
    (net (code "24") (name "Net-(U6-SS)") (class "Default")
      (node (ref "C55") (pin "2") (pinfunction "2_2") (pintype "passive"))
      (node (ref "TP77") (pin "TP") (pinfunction "TP_TP") (pintype "passive"))
      (node (ref "U6") (pin "4") (pinfunction "SS_4") (pintype "passive"))
    )
    (net (code "25") (name "Net-(U6-VSENSE)") (class "Default")
      (node (ref "C49") (pin "2") (pinfunction "2_2") (pintype "passive"))
      (node (ref "R24") (pin "1") (pintype "passive"))
      (node (ref "R27") (pin "2") (pintype "passive"))
      (node (ref "TP78") (pin "TP") (pinfunction "TP_TP") (pintype "passive"))
      (node (ref "U6") (pin "5") (pinfunction "VSENSE_5") (pintype "power_in"))
    )
  )
)
